# Analog_board.net
KiCad netlist of a schematic drawn in EAGLE
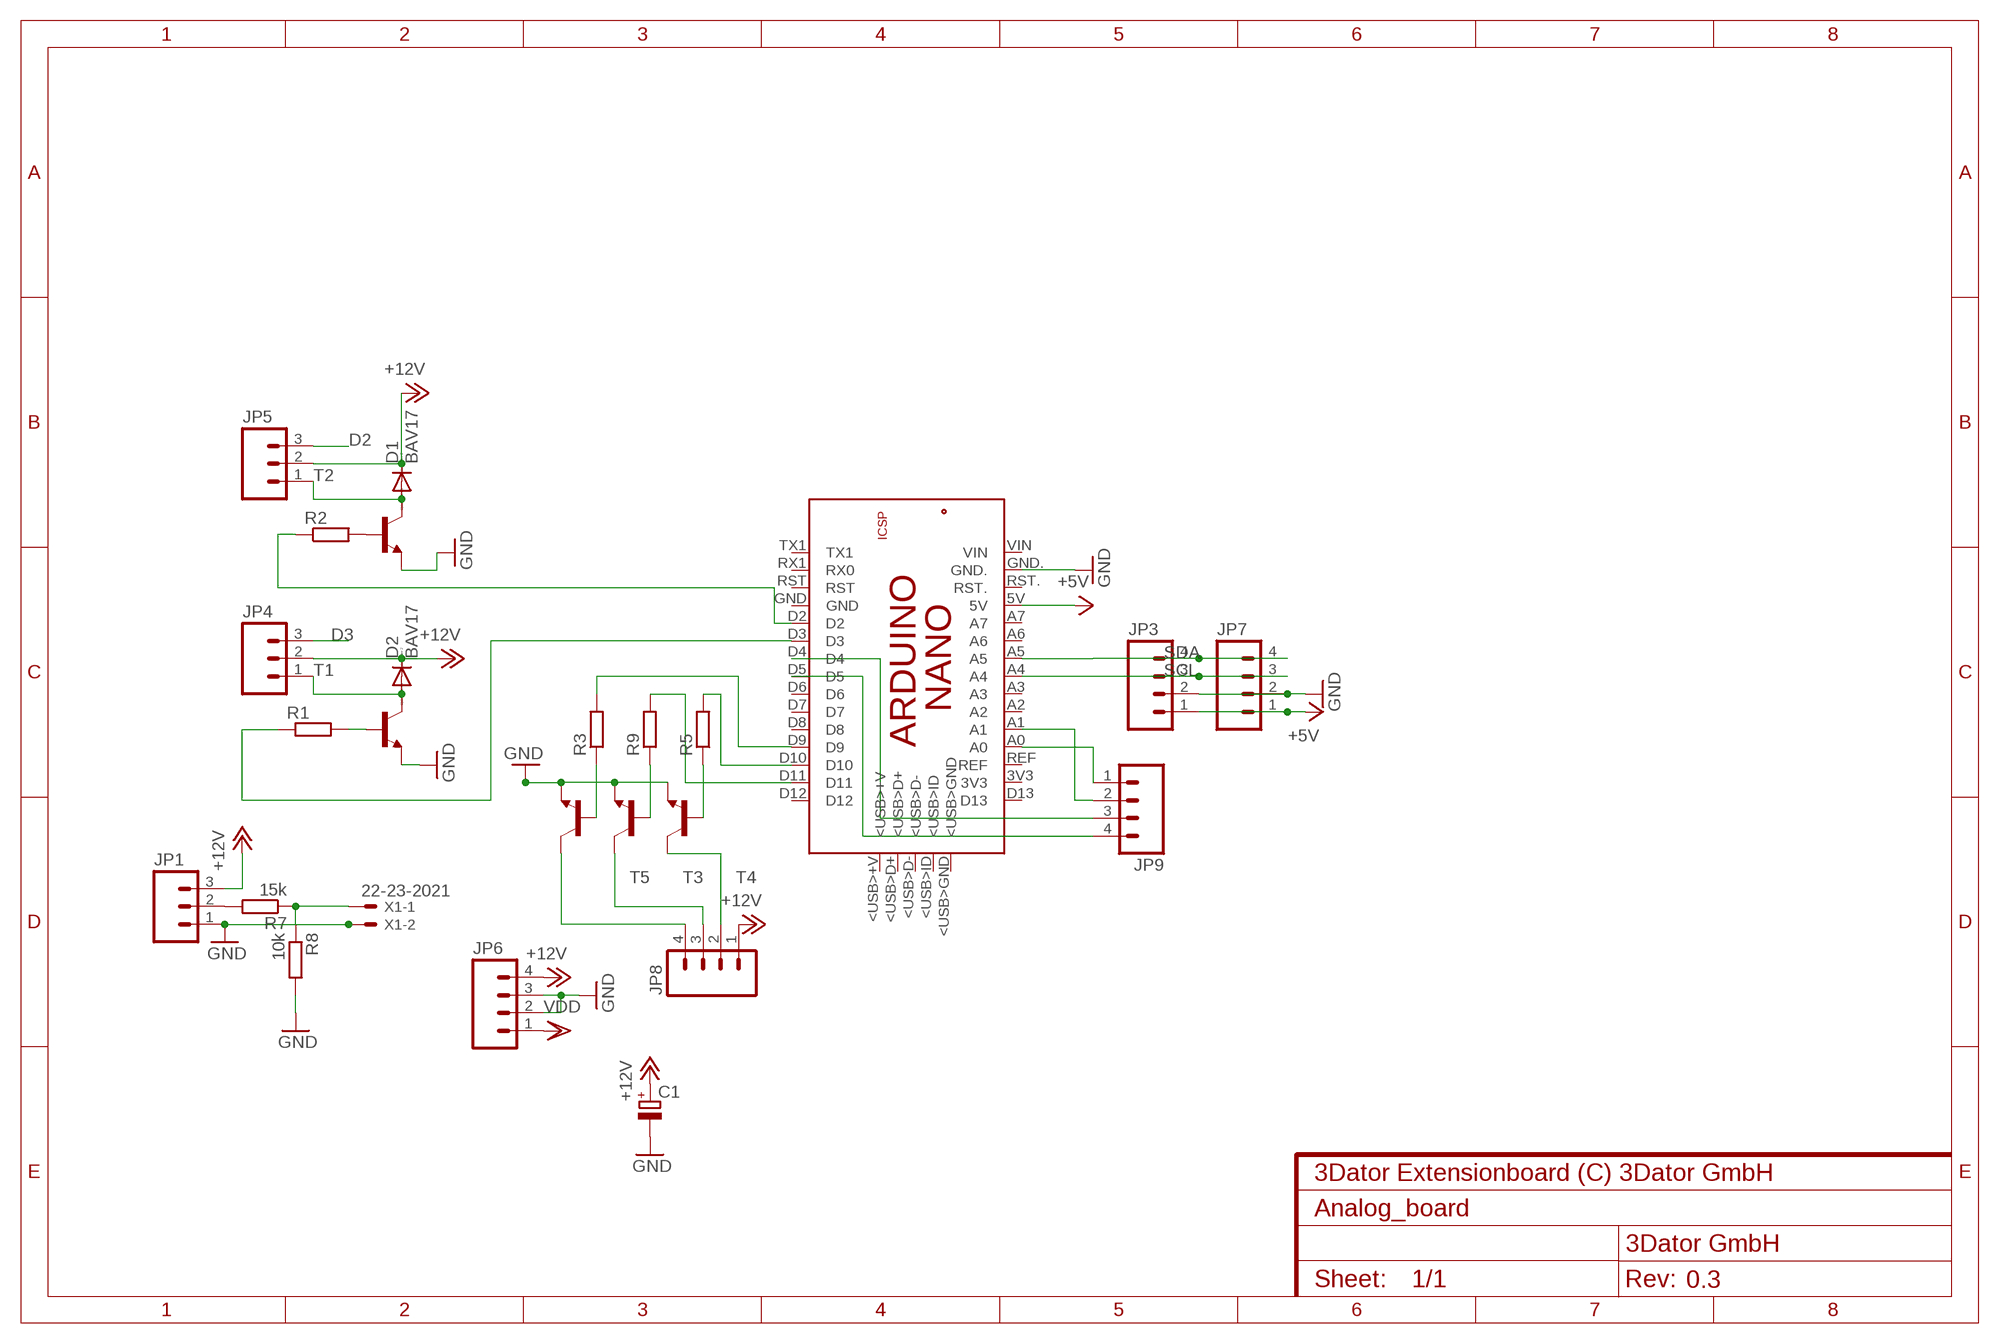
[diagram p0: schematic, sheet 1]

(export (version "E")
  (design (tool "Eeschema 10.0.6"))
  (components
    (comp (ref "C1")
      (value "CPOL-EUE3.5-10")
      (footprint "eagle-import:E3,5-10")
      (libsource (lib "eagle-import") (part "CPOL-EUE3.5-10"))
    )
    (comp (ref "D1")
      (value "BAV17")
      (footprint "eagle-import:DO35-10")
      (libsource (lib "eagle-import") (part "BAV17"))
    )
    (comp (ref "D2")
      (value "BAV17")
      (footprint "eagle-import:DO35-10")
      (libsource (lib "eagle-import") (part "BAV17"))
    )
    (comp (ref "JP1")
      (value "M03POLAR")
      (footprint "eagle-import:MOLEX-1X3")
      (libsource (lib "eagle-import") (part "M03POLAR"))
    )
    (comp (ref "JP3")
      (value "M04POLAR")
      (footprint "eagle-import:MOLEX-1X4")
      (libsource (lib "eagle-import") (part "M04POLAR"))
    )
    (comp (ref "JP4")
      (value "M03POLAR")
      (footprint "eagle-import:MOLEX-1X3")
      (libsource (lib "eagle-import") (part "M03POLAR"))
    )
    (comp (ref "JP5")
      (value "M03POLAR")
      (footprint "eagle-import:MOLEX-1X3")
      (libsource (lib "eagle-import") (part "M03POLAR"))
    )
    (comp (ref "JP6")
      (value "M04POLAR")
      (footprint "eagle-import:MOLEX-1X4")
      (libsource (lib "eagle-import") (part "M04POLAR"))
    )
    (comp (ref "JP7")
      (value "M04POLAR")
      (footprint "eagle-import:MOLEX-1X4")
      (libsource (lib "eagle-import") (part "M04POLAR"))
    )
    (comp (ref "JP8")
      (value "M04POLAR")
      (footprint "eagle-import:MOLEX-1X4")
      (libsource (lib "eagle-import") (part "M04POLAR"))
    )
    (comp (ref "JP9")
      (value "M04POLAR")
      (footprint "eagle-import:MOLEX-1X4")
      (libsource (lib "eagle-import") (part "M04POLAR"))
    )
    (comp (ref "PCB2")
      (value "ARDUINO_NANO")
      (footprint "eagle-import:ARDUINO_NANO")
      (libsource (lib "eagle-import") (part "ARDUINO_NANO"))
    )
    (comp (ref "R1")
      (value "R-EU_0309/12")
      (footprint "eagle-import:0309_12")
      (libsource (lib "eagle-import") (part "R-EU_0309/12"))
    )
    (comp (ref "R2")
      (value "R-EU_0309/10")
      (footprint "eagle-import:0309_10")
      (libsource (lib "eagle-import") (part "R-EU_0309/10"))
    )
    (comp (ref "R3")
      (value "R-EU_0309/10")
      (footprint "eagle-import:0309_10")
      (libsource (lib "eagle-import") (part "R-EU_0309/10"))
    )
    (comp (ref "R5")
      (value "R-EU_0309/10")
      (footprint "eagle-import:0309_10")
      (libsource (lib "eagle-import") (part "R-EU_0309/10"))
    )
    (comp (ref "R7")
      (value "15k")
      (footprint "eagle-import:0309_10")
      (libsource (lib "eagle-import") (part "R-EU_0309/10"))
    )
    (comp (ref "R8")
      (value "10k")
      (footprint "eagle-import:0309_10")
      (libsource (lib "eagle-import") (part "R-EU_0309/10"))
    )
    (comp (ref "R9")
      (value "R-EU_0309/10")
      (footprint "eagle-import:0309_10")
      (libsource (lib "eagle-import") (part "R-EU_0309/10"))
    )
    (comp (ref "T1")
      (value "BC548-NPN-TO92-CBE")
      (footprint "eagle-import:TO92-CBE")
      (libsource (lib "eagle-import") (part "-NPN-TO92-CBEBC548"))
    )
    (comp (ref "T2")
      (value "BC548-NPN-TO92-CBE")
      (footprint "eagle-import:TO92-CBE")
      (libsource (lib "eagle-import") (part "-NPN-TO92-CBEBC548"))
    )
    (comp (ref "T3")
      (value "BC548-NPN-TO92-CBE")
      (footprint "eagle-import:TO92-CBE")
      (libsource (lib "eagle-import") (part "-NPN-TO92-CBEBC548"))
    )
    (comp (ref "T4")
      (value "BC548-NPN-TO92-CBE")
      (footprint "eagle-import:TO92-CBE")
      (libsource (lib "eagle-import") (part "-NPN-TO92-CBEBC548"))
    )
    (comp (ref "T5")
      (value "BC548-NPN-TO92-CBE")
      (footprint "eagle-import:TO92-CBE")
      (libsource (lib "eagle-import") (part "-NPN-TO92-CBEBC548"))
    )
    (comp (ref "X1")
      (value "22-23-2021")
      (footprint "eagle-import:22-23-2021")
      (fields (field (name "MF") "MOLEX"))
      (libsource (lib "eagle-import") (part "22-23-2021"))
    )
  )
  (nets
    (net (code "1") (name "+5V") (class "Default")
      (node (ref "JP3") (pin "1") (pinfunction "1_1") (pintype "passive"))
      (node (ref "JP7") (pin "1") (pinfunction "1_1") (pintype "passive"))
      (node (ref "PCB2") (pin "5V") (pinfunction "5V_5V") (pintype "bidirectional"))
    )
    (net (code "2") (name "+12V") (class "Default")
      (node (ref "C1") (pin "+") (pinfunction "+_+") (pintype "passive"))
      (node (ref "D1") (pin "C") (pinfunction "C_C") (pintype "passive"))
      (node (ref "D2") (pin "C") (pinfunction "C_C") (pintype "passive"))
      (node (ref "JP1") (pin "3") (pinfunction "3_3") (pintype "passive"))
      (node (ref "JP4") (pin "2") (pinfunction "2_2") (pintype "passive"))
      (node (ref "JP5") (pin "2") (pinfunction "2_2") (pintype "passive"))
      (node (ref "JP6") (pin "4") (pinfunction "4_4") (pintype "passive"))
      (node (ref "JP8") (pin "1") (pinfunction "1_1") (pintype "passive"))
    )
    (net (code "3") (name "/D2") (class "Default")
      (node (ref "JP5") (pin "3") (pinfunction "3_3") (pintype "passive"))
    )
    (net (code "4") (name "/D3") (class "Default")
      (node (ref "JP4") (pin "3") (pinfunction "3_3") (pintype "passive"))
    )
    (net (code "5") (name "/SCL") (class "Default")
      (node (ref "JP3") (pin "4") (pinfunction "4_4") (pintype "passive"))
      (node (ref "JP7") (pin "4") (pinfunction "4_4") (pintype "passive"))
      (node (ref "PCB2") (pin "A5") (pinfunction "A5_A5") (pintype "bidirectional"))
    )
    (net (code "6") (name "/SDA") (class "Default")
      (node (ref "JP3") (pin "3") (pinfunction "3_3") (pintype "passive"))
      (node (ref "JP7") (pin "3") (pinfunction "3_3") (pintype "passive"))
      (node (ref "PCB2") (pin "A4") (pinfunction "A4_A4") (pintype "bidirectional"))
    )
    (net (code "7") (name "GND") (class "Default")
      (node (ref "C1") (pin "-") (pinfunction "-_-") (pintype "passive"))
      (node (ref "JP1") (pin "1") (pinfunction "1_1") (pintype "passive"))
      (node (ref "JP3") (pin "2") (pinfunction "2_2") (pintype "passive"))
      (node (ref "JP6") (pin "2") (pinfunction "2_2") (pintype "passive"))
      (node (ref "JP6") (pin "3") (pinfunction "3_3") (pintype "passive"))
      (node (ref "JP7") (pin "2") (pinfunction "2_2") (pintype "passive"))
      (node (ref "PCB2") (pin "GND.") (pinfunction "GND._GND.") (pintype "bidirectional"))
      (node (ref "R8") (pin "2") (pinfunction "2_2") (pintype "passive"))
      (node (ref "T1") (pin "E") (pinfunction "E_E") (pintype "passive"))
      (node (ref "T2") (pin "E") (pinfunction "E_E") (pintype "passive"))
      (node (ref "T3") (pin "E") (pinfunction "E_E") (pintype "passive"))
      (node (ref "T4") (pin "E") (pinfunction "E_E") (pintype "passive"))
      (node (ref "T5") (pin "E") (pinfunction "E_E") (pintype "passive"))
      (node (ref "X1") (pin "2") (pinfunction "S_2") (pintype "passive"))
    )
    (net (code "8") (name "Net-(D1-PadA)") (class "Default")
      (node (ref "D1") (pin "A") (pinfunction "A_A") (pintype "passive"))
      (node (ref "JP5") (pin "1") (pinfunction "1_1") (pintype "passive"))
      (node (ref "T2") (pin "C") (pinfunction "C_C") (pintype "passive"))
    )
    (net (code "9") (name "Net-(D2-PadA)") (class "Default")
      (node (ref "D2") (pin "A") (pinfunction "A_A") (pintype "passive"))
      (node (ref "JP4") (pin "1") (pinfunction "1_1") (pintype "passive"))
      (node (ref "T1") (pin "C") (pinfunction "C_C") (pintype "passive"))
    )
    (net (code "10") (name "Net-(JP1-Pad2)") (class "Default")
      (node (ref "JP1") (pin "2") (pinfunction "2_2") (pintype "passive"))
      (node (ref "R7") (pin "2") (pinfunction "2_2") (pintype "passive"))
    )
    (net (code "11") (name "Net-(JP8-Pad2)") (class "Default")
      (node (ref "JP8") (pin "2") (pinfunction "2_2") (pintype "passive"))
      (node (ref "T4") (pin "C") (pinfunction "C_C") (pintype "passive"))
    )
    (net (code "12") (name "Net-(JP8-Pad3)") (class "Default")
      (node (ref "JP8") (pin "3") (pinfunction "3_3") (pintype "passive"))
      (node (ref "T3") (pin "C") (pinfunction "C_C") (pintype "passive"))
    )
    (net (code "13") (name "Net-(JP8-Pad4)") (class "Default")
      (node (ref "JP8") (pin "4") (pinfunction "4_4") (pintype "passive"))
      (node (ref "T5") (pin "C") (pinfunction "C_C") (pintype "passive"))
    )
    (net (code "14") (name "Net-(JP9-Pad1)") (class "Default")
      (node (ref "JP9") (pin "1") (pinfunction "1_1") (pintype "passive"))
      (node (ref "PCB2") (pin "A0") (pinfunction "A0_A0") (pintype "bidirectional"))
    )
    (net (code "15") (name "Net-(JP9-Pad2)") (class "Default")
      (node (ref "JP9") (pin "2") (pinfunction "2_2") (pintype "passive"))
      (node (ref "PCB2") (pin "A1") (pinfunction "A1_A1") (pintype "bidirectional"))
    )
    (net (code "16") (name "Net-(JP9-Pad3)") (class "Default")
      (node (ref "JP9") (pin "3") (pinfunction "3_3") (pintype "passive"))
      (node (ref "PCB2") (pin "D4") (pinfunction "D4_D4") (pintype "bidirectional"))
    )
    (net (code "17") (name "Net-(JP9-Pad4)") (class "Default")
      (node (ref "JP9") (pin "4") (pinfunction "4_4") (pintype "passive"))
      (node (ref "PCB2") (pin "D5") (pinfunction "D5_D5") (pintype "bidirectional"))
    )
    (net (code "18") (name "Net-(PCB2-PadD2)") (class "Default")
      (node (ref "PCB2") (pin "D2") (pinfunction "D2_D2") (pintype "bidirectional"))
      (node (ref "R2") (pin "1") (pinfunction "1_1") (pintype "passive"))
    )
    (net (code "19") (name "Net-(PCB2-PadD3)") (class "Default")
      (node (ref "PCB2") (pin "D3") (pinfunction "D3_D3") (pintype "bidirectional"))
      (node (ref "R1") (pin "1") (pinfunction "1_1") (pintype "passive"))
    )
    (net (code "20") (name "Net-(PCB2-PadD9)") (class "Default")
      (node (ref "PCB2") (pin "D9") (pinfunction "D9_D9") (pintype "bidirectional"))
      (node (ref "R3") (pin "2") (pinfunction "2_2") (pintype "passive"))
    )
    (net (code "21") (name "Net-(PCB2-PadD10)") (class "Default")
      (node (ref "PCB2") (pin "D10") (pinfunction "D10_D10") (pintype "bidirectional"))
      (node (ref "R5") (pin "2") (pinfunction "2_2") (pintype "passive"))
    )
    (net (code "22") (name "Net-(PCB2-PadD11)") (class "Default")
      (node (ref "PCB2") (pin "D11") (pinfunction "D11_D11") (pintype "bidirectional"))
      (node (ref "R9") (pin "2") (pinfunction "2_2") (pintype "passive"))
    )
    (net (code "23") (name "Net-(R1-Pad2)") (class "Default")
      (node (ref "R1") (pin "2") (pinfunction "2_2") (pintype "passive"))
      (node (ref "T1") (pin "B") (pinfunction "B_B") (pintype "passive"))
    )
    (net (code "24") (name "Net-(R2-Pad2)") (class "Default")
      (node (ref "R2") (pin "2") (pinfunction "2_2") (pintype "passive"))
      (node (ref "T2") (pin "B") (pinfunction "B_B") (pintype "passive"))
    )
    (net (code "25") (name "Net-(R3-Pad1)") (class "Default")
      (node (ref "R3") (pin "1") (pinfunction "1_1") (pintype "passive"))
      (node (ref "T5") (pin "B") (pinfunction "B_B") (pintype "passive"))
    )
    (net (code "26") (name "Net-(R5-Pad1)") (class "Default")
      (node (ref "R5") (pin "1") (pinfunction "1_1") (pintype "passive"))
      (node (ref "T4") (pin "B") (pinfunction "B_B") (pintype "passive"))
    )
    (net (code "27") (name "Net-(R9-Pad1)") (class "Default")
      (node (ref "R9") (pin "1") (pinfunction "1_1") (pintype "passive"))
      (node (ref "T3") (pin "B") (pinfunction "B_B") (pintype "passive"))
    )
    (net (code "28") (name "Net-(X1A-S)") (class "Default")
      (node (ref "R7") (pin "1") (pinfunction "1_1") (pintype "passive"))
      (node (ref "R8") (pin "1") (pinfunction "1_1") (pintype "passive"))
      (node (ref "X1") (pin "1") (pinfunction "S_1") (pintype "passive"))
    )
    (net (code "29") (name "VDD") (class "Default")
      (node (ref "JP6") (pin "1") (pinfunction "1_1") (pintype "passive"))
    )
    (net (code "30") (name "unconnected-(PCB2-Pad3V3)") (class "Default")
      (node (ref "PCB2") (pin "3V3") (pinfunction "3V3_3V3") (pintype "bidirectional"))
    )
    (net (code "31") (name "unconnected-(PCB2-Pad5V.)") (class "Default")
      (node (ref "PCB2") (pin "5V.") (pinfunction "5V._5V.") (pintype "bidirectional"))
    )
    (net (code "32") (name "unconnected-(PCB2-Pad<USB>+V)") (class "Default")
      (node (ref "PCB2") (pin "<USB>+V") (pinfunction "<USB>+V_<USB>+V") (pintype "bidirectional"))
    )
    (net (code "33") (name "unconnected-(PCB2-Pad<USB>D+)") (class "Default")
      (node (ref "PCB2") (pin "<USB>D+") (pinfunction "<USB>D+_<USB>D+") (pintype "bidirectional"))
    )
    (net (code "34") (name "unconnected-(PCB2-Pad<USB>D-)") (class "Default")
      (node (ref "PCB2") (pin "<USB>D-") (pinfunction "<USB>D-_<USB>D-") (pintype "bidirectional"))
    )
    (net (code "35") (name "unconnected-(PCB2-Pad<USB>GND)") (class "Default")
      (node (ref "PCB2") (pin "<USB>GND") (pinfunction "<USB>GND_<USB>GND") (pintype "bidirectional"))
    )
    (net (code "36") (name "unconnected-(PCB2-Pad<USB>ID)") (class "Default")
      (node (ref "PCB2") (pin "<USB>ID") (pinfunction "<USB>ID_<USB>ID") (pintype "bidirectional"))
    )
    (net (code "37") (name "unconnected-(PCB2-PadA2)") (class "Default")
      (node (ref "PCB2") (pin "A2") (pinfunction "A2_A2") (pintype "bidirectional"))
    )
    (net (code "38") (name "unconnected-(PCB2-PadA3)") (class "Default")
      (node (ref "PCB2") (pin "A3") (pinfunction "A3_A3") (pintype "bidirectional"))
    )
    (net (code "39") (name "unconnected-(PCB2-PadA6)") (class "Default")
      (node (ref "PCB2") (pin "A6") (pinfunction "A6_A6") (pintype "bidirectional"))
    )
    (net (code "40") (name "unconnected-(PCB2-PadA7)") (class "Default")
      (node (ref "PCB2") (pin "A7") (pinfunction "A7_A7") (pintype "bidirectional"))
    )
    (net (code "41") (name "unconnected-(PCB2-PadD6)") (class "Default")
      (node (ref "PCB2") (pin "D6") (pinfunction "D6_D6") (pintype "bidirectional"))
    )
    (net (code "42") (name "unconnected-(PCB2-PadD7)") (class "Default")
      (node (ref "PCB2") (pin "D7") (pinfunction "D7_D7") (pintype "bidirectional"))
    )
    (net (code "43") (name "unconnected-(PCB2-PadD8)") (class "Default")
      (node (ref "PCB2") (pin "D8") (pinfunction "D8_D8") (pintype "bidirectional"))
    )
    (net (code "44") (name "unconnected-(PCB2-PadD12)") (class "Default")
      (node (ref "PCB2") (pin "D12") (pinfunction "D12_D12") (pintype "bidirectional"))
    )
    (net (code "45") (name "unconnected-(PCB2-PadD13)") (class "Default")
      (node (ref "PCB2") (pin "D13") (pinfunction "D13_D13") (pintype "bidirectional"))
    )
    (net (code "46") (name "unconnected-(PCB2-PadGND)") (class "Default")
      (node (ref "PCB2") (pin "GND") (pinfunction "GND_GND") (pintype "bidirectional"))
    )
    (net (code "47") (name "unconnected-(PCB2-PadGND_)") (class "Default")
      (node (ref "PCB2") (pin "GND_") (pinfunction "GND__GND_") (pintype "bidirectional"))
    )
    (net (code "48") (name "unconnected-(PCB2-PadMISO)") (class "Default")
      (node (ref "PCB2") (pin "MISO") (pinfunction "MISO_MISO") (pintype "bidirectional"))
    )
    (net (code "49") (name "unconnected-(PCB2-PadMOSI)") (class "Default")
      (node (ref "PCB2") (pin "MOSI") (pinfunction "MOSI_MOSI") (pintype "bidirectional"))
    )
    (net (code "50") (name "unconnected-(PCB2-PadREF)") (class "Default")
      (node (ref "PCB2") (pin "REF") (pinfunction "REF_REF") (pintype "bidirectional"))
    )
    (net (code "51") (name "unconnected-(PCB2-PadRESET..)") (class "Default")
      (node (ref "PCB2") (pin "RESET..") (pinfunction "RESET.._RESET..") (pintype "bidirectional"))
    )
    (net (code "52") (name "unconnected-(PCB2-PadRST)") (class "Default")
      (node (ref "PCB2") (pin "RST") (pinfunction "RST_RST") (pintype "bidirectional"))
    )
    (net (code "53") (name "unconnected-(PCB2-PadRST.)") (class "Default")
      (node (ref "PCB2") (pin "RST.") (pinfunction "RST._RST.") (pintype "bidirectional"))
    )
    (net (code "54") (name "unconnected-(PCB2-PadSCK)") (class "Default")
      (node (ref "PCB2") (pin "SCK") (pinfunction "SCK_SCK") (pintype "bidirectional"))
    )
    (net (code "55") (name "unconnected-(PCB2-PadTX1)") (class "Default")
      (node (ref "PCB2") (pin "TX1") (pinfunction "TX1_TX1") (pintype "bidirectional"))
    )
    (net (code "56") (name "unconnected-(PCB2-PadVIN)") (class "Default")
      (node (ref "PCB2") (pin "VIN") (pinfunction "VIN_VIN") (pintype "bidirectional"))
    )
    (net (code "57") (name "unconnected-(PCB2-RX0-PadRX1)") (class "Default")
      (node (ref "PCB2") (pin "RX1") (pinfunction "RX0_RX1") (pintype "bidirectional"))
    )
  )
)
